# GPSBoard_L30.net
KiCad netlist of a schematic drawn in Altium Designer
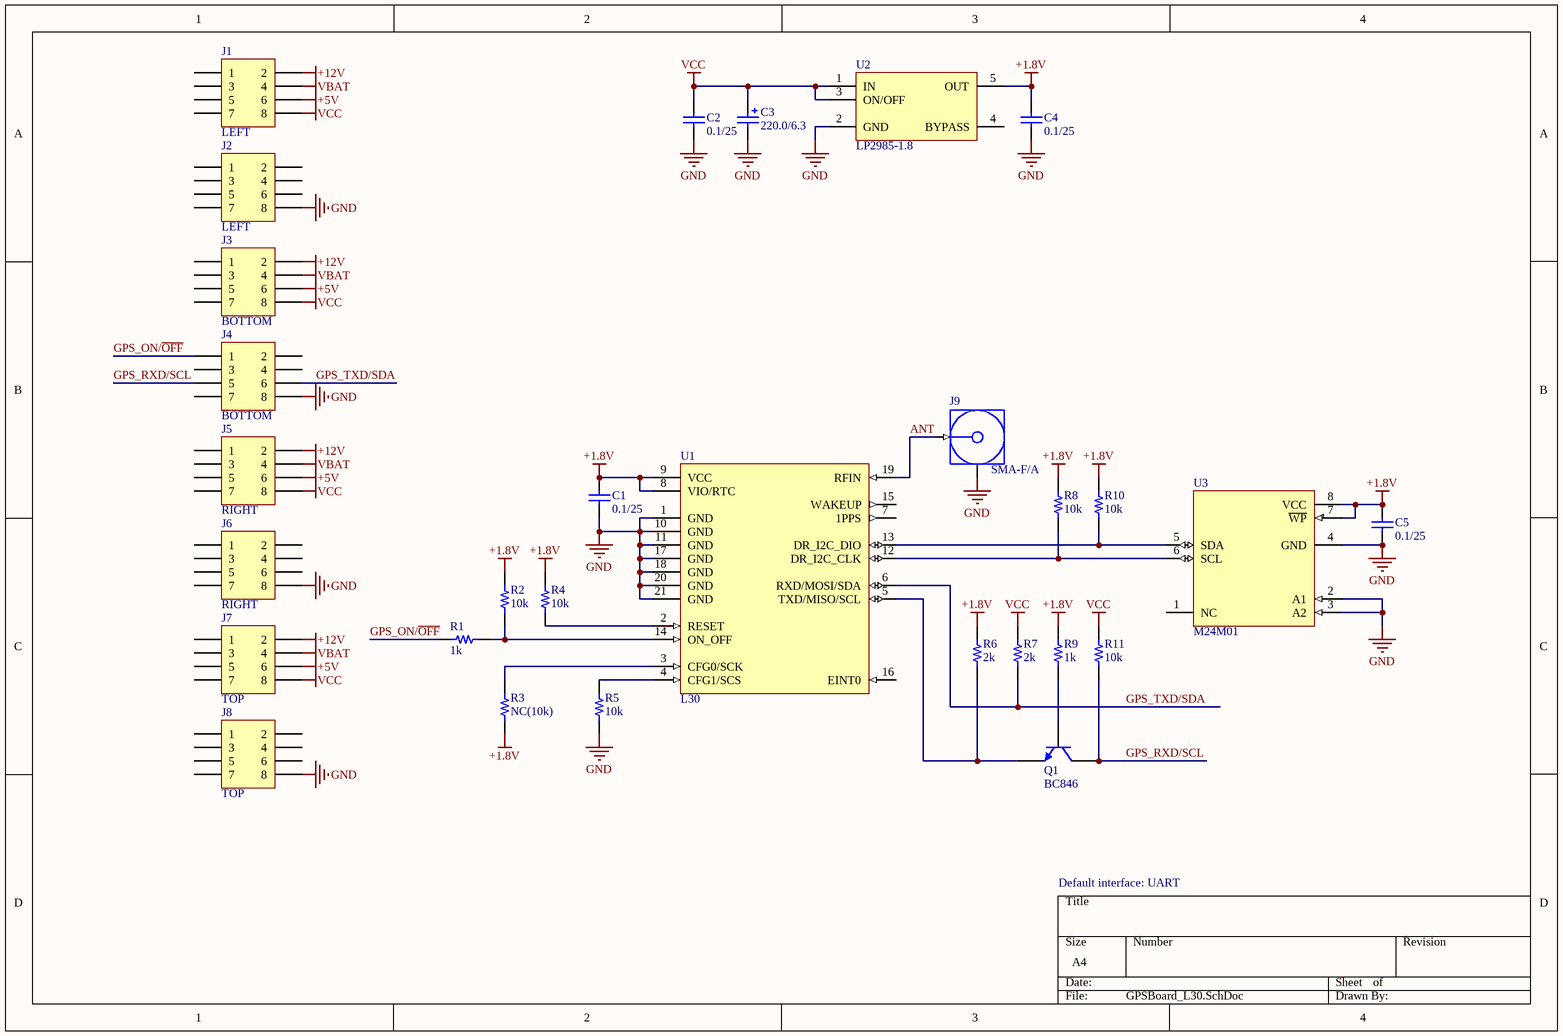
[diagram p0: GPSBoard_L30.SchDoc]

(export (version "E")
  (design (tool "Eeschema 10.0.6"))
  (components
    (comp (ref "C1")
      (value "0.1/25")
      (footprint "CAP0402")
      (description "Ceramic chip capacitor 0402")
      (fields
        (field (name "PARTNUMBER") "CAP0402")
        (field (name "VOLTAGE") "25")
        (field (name "AUTHOR") "oiezhov")
      )
      (libsource (lib "Library") (part "Capacitor"))
    )
    (comp (ref "C2")
      (value "0.1/25")
      (footprint "CAP0402")
      (description "Ceramic chip capacitor 0402")
      (fields
        (field (name "PARTNUMBER") "CAP0402")
        (field (name "VOLTAGE") "25")
        (field (name "AUTHOR") "oiezhov")
      )
      (libsource (lib "Library") (part "Capacitor"))
    )
    (comp (ref "C3")
      (value "220.0/6.3")
      (footprint "SMC")
      (description "Standard tantalum SMT capacitor, size C")
      (fields
        (field (name "PARTNUMBER") "TAJC")
        (field (name "VOLTAGE") "6.3")
        (field (name "AUTHOR") "oiezhov")
      )
      (libsource (lib "Library") (part "Polar capacitor"))
    )
    (comp (ref "C4")
      (value "0.1/25")
      (footprint "CAP0402")
      (description "Ceramic chip capacitor 0402")
      (fields
        (field (name "PARTNUMBER") "CAP0402")
        (field (name "VOLTAGE") "25")
        (field (name "AUTHOR") "oiezhov")
      )
      (libsource (lib "Library") (part "Capacitor"))
    )
    (comp (ref "C5")
      (value "0.1/25")
      (footprint "CAP0402")
      (description "Ceramic chip capacitor 0402")
      (fields
        (field (name "PARTNUMBER") "CAP0402")
        (field (name "VOLTAGE") "25")
        (field (name "AUTHOR") "oiezhov")
      )
      (libsource (lib "Library") (part "Capacitor"))
    )
    (comp (ref "J1")
      (value "LEFT")
      (footprint "PBDM-8")
      (description "2x4-pin header, pitch 2.54 mm")
      (fields (field (name "PARTNUMBER") "PBDM-8") (field (name "AUTHOR") "oiezhov"))
      (libsource (lib "Library") (part "8-pin dual row connector"))
    )
    (comp (ref "J2")
      (value "LEFT")
      (footprint "PBDM-8")
      (description "2x4-pin header, pitch 2.54 mm")
      (fields (field (name "PARTNUMBER") "PBDM-8") (field (name "AUTHOR") "oiezhov"))
      (libsource (lib "Library") (part "8-pin dual row connector"))
    )
    (comp (ref "J3")
      (value "BOTTOM")
      (footprint "PBDM-8")
      (description "2x4-pin header, pitch 2.54 mm")
      (fields (field (name "PARTNUMBER") "PBDM-8") (field (name "AUTHOR") "oiezhov"))
      (libsource (lib "Library") (part "8-pin dual row connector"))
    )
    (comp (ref "J4")
      (value "BOTTOM")
      (footprint "PBDM-8")
      (description "2x4-pin header, pitch 2.54 mm")
      (fields (field (name "PARTNUMBER") "PBDM-8") (field (name "AUTHOR") "oiezhov"))
      (libsource (lib "Library") (part "8-pin dual row connector"))
    )
    (comp (ref "J5")
      (value "RIGHT")
      (footprint "PBDM-8")
      (description "2x4-pin header, pitch 2.54 mm")
      (fields (field (name "PARTNUMBER") "PBDM-8") (field (name "AUTHOR") "oiezhov"))
      (libsource (lib "Library") (part "8-pin dual row connector"))
    )
    (comp (ref "J6")
      (value "RIGHT")
      (footprint "PBDM-8")
      (description "2x4-pin header, pitch 2.54 mm")
      (fields (field (name "PARTNUMBER") "PBDM-8") (field (name "AUTHOR") "oiezhov"))
      (libsource (lib "Library") (part "8-pin dual row connector"))
    )
    (comp (ref "J7")
      (value "TOP")
      (footprint "PBDM-8")
      (description "2x4-pin header, pitch 2.54 mm")
      (fields (field (name "PARTNUMBER") "PBDM-8") (field (name "AUTHOR") "oiezhov"))
      (libsource (lib "Library") (part "8-pin dual row connector"))
    )
    (comp (ref "J8")
      (value "TOP")
      (footprint "PBDM-8")
      (description "2x4-pin header, pitch 2.54 mm")
      (fields (field (name "PARTNUMBER") "PBDM-8") (field (name "AUTHOR") "oiezhov"))
      (libsource (lib "Library") (part "8-pin dual row connector"))
    )
    (comp (ref "J9")
      (value "SMA-F/A")
      (footprint "SMA-F/A")
      (description "Angle SMA female connector")
      (fields (field (name "AUTHOR") "oiezhov"))
      (libsource (lib "Library") (part "SMA"))
    )
    (comp (ref "Q1")
      (value "BC846")
      (footprint "SOT23")
      (description "NPN Silicon AF Transistor")
      (fields (field (name "AUTHOR") "oiezhov"))
      (libsource (lib "Library") (part "BC846"))
    )
    (comp (ref "R1")
      (value "1k")
      (footprint "RES0402")
      (description "Ceramic chip resistor")
      (fields (field (name "PARTNUMBER") "RES0402") (field (name "AUTHOR") "oiezhov"))
      (libsource (lib "Library") (part "Resistor"))
    )
    (comp (ref "R2")
      (value "10k")
      (footprint "RES0402")
      (description "Ceramic chip resistor")
      (fields (field (name "PARTNUMBER") "RES0402") (field (name "AUTHOR") "oiezhov"))
      (libsource (lib "Library") (part "Resistor"))
    )
    (comp (ref "R3")
      (value "NC(10k)")
      (footprint "RES0402")
      (description "Ceramic chip resistor")
      (fields (field (name "PARTNUMBER") "RES0402") (field (name "AUTHOR") "oiezhov"))
      (libsource (lib "Library") (part "Resistor"))
    )
    (comp (ref "R4")
      (value "10k")
      (footprint "RES0402")
      (description "Ceramic chip resistor")
      (fields (field (name "PARTNUMBER") "RES0402") (field (name "AUTHOR") "oiezhov"))
      (libsource (lib "Library") (part "Resistor"))
    )
    (comp (ref "R5")
      (value "10k")
      (footprint "RES0402")
      (description "Ceramic chip resistor")
      (fields (field (name "PARTNUMBER") "RES0402") (field (name "AUTHOR") "oiezhov"))
      (libsource (lib "Library") (part "Resistor"))
    )
    (comp (ref "R6")
      (value "2k")
      (footprint "RES0402")
      (description "Ceramic chip resistor")
      (fields (field (name "PARTNUMBER") "RES0402") (field (name "AUTHOR") "oiezhov"))
      (libsource (lib "Library") (part "Resistor"))
    )
    (comp (ref "R7")
      (value "2k")
      (footprint "RES0402")
      (description "Ceramic chip resistor")
      (fields (field (name "PARTNUMBER") "RES0402") (field (name "AUTHOR") "oiezhov"))
      (libsource (lib "Library") (part "Resistor"))
    )
    (comp (ref "R8")
      (value "10k")
      (footprint "RES0402")
      (description "Ceramic chip resistor")
      (fields (field (name "PARTNUMBER") "RES0402") (field (name "AUTHOR") "oiezhov"))
      (libsource (lib "Library") (part "Resistor"))
    )
    (comp (ref "R9")
      (value "1k")
      (footprint "RES0402")
      (description "Ceramic chip resistor")
      (fields (field (name "PARTNUMBER") "RES0402") (field (name "AUTHOR") "oiezhov"))
      (libsource (lib "Library") (part "Resistor"))
    )
    (comp (ref "R10")
      (value "10k")
      (footprint "RES0402")
      (description "Ceramic chip resistor")
      (fields (field (name "PARTNUMBER") "RES0402") (field (name "AUTHOR") "oiezhov"))
      (libsource (lib "Library") (part "Resistor"))
    )
    (comp (ref "R11")
      (value "10k")
      (footprint "RES0402")
      (description "Ceramic chip resistor")
      (fields (field (name "PARTNUMBER") "RES0402") (field (name "AUTHOR") "oiezhov"))
      (libsource (lib "Library") (part "Resistor"))
    )
    (comp (ref "U1")
      (value "L30")
      (footprint "Quectel_L30")
      (description "GPS Engine")
      (fields (field (name "AUTHOR") "oiezhov"))
      (libsource (lib "Library") (part "L30"))
    )
    (comp (ref "U2")
      (value "LP2985-1.8")
      (footprint "SOT23-5")
      (description "150-mA Low-Noise Low-Dropout Regulator with Shutdown")
      (fields (field (name "AUTHOR") "oiezhov"))
      (libsource (lib "Library") (part "5-pin voltage regulator with ON/OFF and BYPASS"))
    )
    (comp (ref "U3")
      (value "M24M01")
      (footprint "SO8")
      (description "1-Mbit serial I²C bus EEPROM")
      (fields (field (name "AUTHOR") "oiezhov"))
      (libsource (lib "Library") (part "8-pin I2C EEPROM with NC"))
    )
  )
  (nets
    (net (code "1") (name "+1.8V") (class "Default")
      (node (ref "C1") (pin "2") (pinfunction "2_2") (pintype "passive"))
      (node (ref "C4") (pin "2") (pinfunction "2_2") (pintype "passive"))
      (node (ref "C5") (pin "2") (pinfunction "2_2") (pintype "passive"))
      (node (ref "R10") (pin "2") (pinfunction "2_2") (pintype "passive"))
      (node (ref "R2") (pin "1") (pinfunction "1_1") (pintype "passive"))
      (node (ref "R3") (pin "1") (pinfunction "1_1") (pintype "passive"))
      (node (ref "R4") (pin "1") (pinfunction "1_1") (pintype "passive"))
      (node (ref "R6") (pin "1") (pinfunction "1_1") (pintype "passive"))
      (node (ref "R8") (pin "2") (pinfunction "2_2") (pintype "passive"))
      (node (ref "R9") (pin "1") (pinfunction "1_1") (pintype "passive"))
      (node (ref "U1") (pin "8") (pinfunction "VIO/RTC_8") (pintype "power_in"))
      (node (ref "U1") (pin "9") (pinfunction "VCC_9") (pintype "power_in"))
      (node (ref "U2") (pin "5") (pinfunction "OUT_5") (pintype "passive"))
      (node (ref "U3") (pin "7") (pinfunction "~{WP}_7") (pintype "input"))
      (node (ref "U3") (pin "8") (pinfunction "VCC_8") (pintype "power_in"))
    )
    (net (code "2") (name "+5V") (class "Default")
      (node (ref "J1") (pin "6") (pinfunction "6_6") (pintype "passive"))
      (node (ref "J3") (pin "6") (pinfunction "6_6") (pintype "passive"))
      (node (ref "J5") (pin "6") (pinfunction "6_6") (pintype "passive"))
      (node (ref "J7") (pin "6") (pinfunction "6_6") (pintype "passive"))
    )
    (net (code "3") (name "+12V") (class "Default")
      (node (ref "J1") (pin "2") (pinfunction "2_2") (pintype "passive"))
      (node (ref "J3") (pin "2") (pinfunction "2_2") (pintype "passive"))
      (node (ref "J5") (pin "2") (pinfunction "2_2") (pintype "passive"))
      (node (ref "J7") (pin "2") (pinfunction "2_2") (pintype "passive"))
    )
    (net (code "4") (name "/ANT") (class "Default")
      (node (ref "J9") (pin "1") (pinfunction "Signal_1") (pintype "input"))
      (node (ref "U1") (pin "19") (pinfunction "RFIN_19") (pintype "input"))
    )
    (net (code "5") (name "/GPS_ON{slash}~{OFF}") (class "Default")
      (node (ref "J4") (pin "1") (pinfunction "1_1") (pintype "passive"))
      (node (ref "R1") (pin "1") (pinfunction "1_1") (pintype "passive"))
    )
    (net (code "6") (name "/GPS_RXD{slash}SCL") (class "Default")
      (node (ref "J4") (pin "5") (pinfunction "5_5") (pintype "passive"))
      (node (ref "Q1") (pin "3") (pinfunction "C_3") (pintype "passive"))
      (node (ref "R11") (pin "2") (pinfunction "2_2") (pintype "passive"))
    )
    (net (code "7") (name "/GPS_TXD{slash}SDA") (class "Default")
      (node (ref "J4") (pin "6") (pinfunction "6_6") (pintype "passive"))
      (node (ref "R7") (pin "2") (pinfunction "2_2") (pintype "passive"))
      (node (ref "U1") (pin "6") (pinfunction "RXD/MOSI/SDA_6") (pintype "bidirectional"))
    )
    (net (code "8") (name "GND") (class "Default")
      (node (ref "C1") (pin "1") (pinfunction "1_1") (pintype "passive"))
      (node (ref "C2") (pin "1") (pinfunction "1_1") (pintype "passive"))
      (node (ref "C3") (pin "1") (pinfunction "1_1") (pintype "passive"))
      (node (ref "C4") (pin "1") (pinfunction "1_1") (pintype "passive"))
      (node (ref "C5") (pin "1") (pinfunction "1_1") (pintype "passive"))
      (node (ref "J2") (pin "8") (pinfunction "8_8") (pintype "passive"))
      (node (ref "J4") (pin "8") (pinfunction "8_8") (pintype "passive"))
      (node (ref "J6") (pin "8") (pinfunction "8_8") (pintype "passive"))
      (node (ref "J8") (pin "8") (pinfunction "8_8") (pintype "passive"))
      (node (ref "J9") (pin "2") (pinfunction "GND_2") (pintype "power_in"))
      (node (ref "R5") (pin "1") (pinfunction "1_1") (pintype "passive"))
      (node (ref "U1") (pin "1") (pinfunction "GND_1") (pintype "power_in"))
      (node (ref "U1") (pin "10") (pinfunction "GND_10") (pintype "power_in"))
      (node (ref "U1") (pin "11") (pinfunction "GND_11") (pintype "power_in"))
      (node (ref "U1") (pin "17") (pinfunction "GND_17") (pintype "power_in"))
      (node (ref "U1") (pin "18") (pinfunction "GND_18") (pintype "power_in"))
      (node (ref "U1") (pin "20") (pinfunction "GND_20") (pintype "power_in"))
      (node (ref "U1") (pin "21") (pinfunction "GND_21") (pintype "power_in"))
      (node (ref "U2") (pin "2") (pinfunction "GND_2") (pintype "passive"))
      (node (ref "U3") (pin "2") (pinfunction "A1_2") (pintype "input"))
      (node (ref "U3") (pin "3") (pinfunction "A2_3") (pintype "input"))
      (node (ref "U3") (pin "4") (pinfunction "GND_4") (pintype "power_in"))
    )
    (net (code "9") (name "Net-(Q1-B)") (class "Default")
      (node (ref "Q1") (pin "2") (pinfunction "B_2") (pintype "passive"))
      (node (ref "R9") (pin "2") (pinfunction "2_2") (pintype "passive"))
    )
    (net (code "10") (name "Net-(Q1-E)") (class "Default")
      (node (ref "Q1") (pin "1") (pinfunction "E_1") (pintype "passive"))
      (node (ref "R6") (pin "2") (pinfunction "2_2") (pintype "passive"))
      (node (ref "U1") (pin "5") (pinfunction "TXD/MISO/SCL_5") (pintype "bidirectional"))
    )
    (net (code "11") (name "Net-(U1-CFG0{slash}SCK)") (class "Default")
      (node (ref "R3") (pin "2") (pinfunction "2_2") (pintype "passive"))
      (node (ref "U1") (pin "3") (pinfunction "CFG0/SCK_3") (pintype "input"))
    )
    (net (code "12") (name "Net-(U1-CFG1{slash}SCS)") (class "Default")
      (node (ref "R5") (pin "2") (pinfunction "2_2") (pintype "passive"))
      (node (ref "U1") (pin "4") (pinfunction "CFG1/SCS_4") (pintype "input"))
    )
    (net (code "13") (name "Net-(U1-DR_I2C_CLK)") (class "Default")
      (node (ref "R8") (pin "1") (pinfunction "1_1") (pintype "passive"))
      (node (ref "U1") (pin "12") (pinfunction "DR_I2C_CLK_12") (pintype "bidirectional"))
      (node (ref "U3") (pin "6") (pinfunction "SCL_6") (pintype "bidirectional"))
    )
    (net (code "14") (name "Net-(U1-DR_I2C_DIO)") (class "Default")
      (node (ref "R10") (pin "1") (pinfunction "1_1") (pintype "passive"))
      (node (ref "U1") (pin "13") (pinfunction "DR_I2C_DIO_13") (pintype "bidirectional"))
      (node (ref "U3") (pin "5") (pinfunction "SDA_5") (pintype "bidirectional"))
    )
    (net (code "15") (name "Net-(U1-ON_OFF)") (class "Default")
      (node (ref "R1") (pin "2") (pinfunction "2_2") (pintype "passive"))
      (node (ref "R2") (pin "2") (pinfunction "2_2") (pintype "passive"))
      (node (ref "U1") (pin "14") (pinfunction "ON_OFF_14") (pintype "input"))
    )
    (net (code "16") (name "Net-(U1-RESET)") (class "Default")
      (node (ref "R4") (pin "2") (pinfunction "2_2") (pintype "passive"))
      (node (ref "U1") (pin "2") (pinfunction "RESET_2") (pintype "input"))
    )
    (net (code "17") (name "VBAT") (class "Default")
      (node (ref "J1") (pin "4") (pinfunction "4_4") (pintype "passive"))
      (node (ref "J3") (pin "4") (pinfunction "4_4") (pintype "passive"))
      (node (ref "J5") (pin "4") (pinfunction "4_4") (pintype "passive"))
      (node (ref "J7") (pin "4") (pinfunction "4_4") (pintype "passive"))
    )
    (net (code "18") (name "VCC") (class "Default")
      (node (ref "C2") (pin "2") (pinfunction "2_2") (pintype "passive"))
      (node (ref "C3") (pin "2") (pinfunction "2_2") (pintype "passive"))
      (node (ref "J1") (pin "8") (pinfunction "8_8") (pintype "passive"))
      (node (ref "J3") (pin "8") (pinfunction "8_8") (pintype "passive"))
      (node (ref "J5") (pin "8") (pinfunction "8_8") (pintype "passive"))
      (node (ref "J7") (pin "8") (pinfunction "8_8") (pintype "passive"))
      (node (ref "R11") (pin "1") (pinfunction "1_1") (pintype "passive"))
      (node (ref "R7") (pin "1") (pinfunction "1_1") (pintype "passive"))
      (node (ref "U2") (pin "1") (pinfunction "IN_1") (pintype "passive"))
      (node (ref "U2") (pin "3") (pinfunction "ON/OFF_3") (pintype "passive"))
    )
    (net (code "19") (name "unconnected-(J1-Pad1)") (class "Default")
      (node (ref "J1") (pin "1") (pinfunction "1_1") (pintype "passive"))
    )
    (net (code "20") (name "unconnected-(J1-Pad3)") (class "Default")
      (node (ref "J1") (pin "3") (pinfunction "3_3") (pintype "passive"))
    )
    (net (code "21") (name "unconnected-(J1-Pad5)") (class "Default")
      (node (ref "J1") (pin "5") (pinfunction "5_5") (pintype "passive"))
    )
    (net (code "22") (name "unconnected-(J1-Pad7)") (class "Default")
      (node (ref "J1") (pin "7") (pinfunction "7_7") (pintype "passive"))
    )
    (net (code "23") (name "unconnected-(J2-Pad1)") (class "Default")
      (node (ref "J2") (pin "1") (pinfunction "1_1") (pintype "passive"))
    )
    (net (code "24") (name "unconnected-(J2-Pad2)") (class "Default")
      (node (ref "J2") (pin "2") (pinfunction "2_2") (pintype "passive"))
    )
    (net (code "25") (name "unconnected-(J2-Pad3)") (class "Default")
      (node (ref "J2") (pin "3") (pinfunction "3_3") (pintype "passive"))
    )
    (net (code "26") (name "unconnected-(J2-Pad4)") (class "Default")
      (node (ref "J2") (pin "4") (pinfunction "4_4") (pintype "passive"))
    )
    (net (code "27") (name "unconnected-(J2-Pad5)") (class "Default")
      (node (ref "J2") (pin "5") (pinfunction "5_5") (pintype "passive"))
    )
    (net (code "28") (name "unconnected-(J2-Pad6)") (class "Default")
      (node (ref "J2") (pin "6") (pinfunction "6_6") (pintype "passive"))
    )
    (net (code "29") (name "unconnected-(J2-Pad7)") (class "Default")
      (node (ref "J2") (pin "7") (pinfunction "7_7") (pintype "passive"))
    )
    (net (code "30") (name "unconnected-(J3-Pad1)") (class "Default")
      (node (ref "J3") (pin "1") (pinfunction "1_1") (pintype "passive"))
    )
    (net (code "31") (name "unconnected-(J3-Pad3)") (class "Default")
      (node (ref "J3") (pin "3") (pinfunction "3_3") (pintype "passive"))
    )
    (net (code "32") (name "unconnected-(J3-Pad5)") (class "Default")
      (node (ref "J3") (pin "5") (pinfunction "5_5") (pintype "passive"))
    )
    (net (code "33") (name "unconnected-(J3-Pad7)") (class "Default")
      (node (ref "J3") (pin "7") (pinfunction "7_7") (pintype "passive"))
    )
    (net (code "34") (name "unconnected-(J4-Pad2)") (class "Default")
      (node (ref "J4") (pin "2") (pinfunction "2_2") (pintype "passive"))
    )
    (net (code "35") (name "unconnected-(J4-Pad3)") (class "Default")
      (node (ref "J4") (pin "3") (pinfunction "3_3") (pintype "passive"))
    )
    (net (code "36") (name "unconnected-(J4-Pad4)") (class "Default")
      (node (ref "J4") (pin "4") (pinfunction "4_4") (pintype "passive"))
    )
    (net (code "37") (name "unconnected-(J4-Pad7)") (class "Default")
      (node (ref "J4") (pin "7") (pinfunction "7_7") (pintype "passive"))
    )
    (net (code "38") (name "unconnected-(J5-Pad1)") (class "Default")
      (node (ref "J5") (pin "1") (pinfunction "1_1") (pintype "passive"))
    )
    (net (code "39") (name "unconnected-(J5-Pad3)") (class "Default")
      (node (ref "J5") (pin "3") (pinfunction "3_3") (pintype "passive"))
    )
    (net (code "40") (name "unconnected-(J5-Pad5)") (class "Default")
      (node (ref "J5") (pin "5") (pinfunction "5_5") (pintype "passive"))
    )
    (net (code "41") (name "unconnected-(J5-Pad7)") (class "Default")
      (node (ref "J5") (pin "7") (pinfunction "7_7") (pintype "passive"))
    )
    (net (code "42") (name "unconnected-(J6-Pad1)") (class "Default")
      (node (ref "J6") (pin "1") (pinfunction "1_1") (pintype "passive"))
    )
    (net (code "43") (name "unconnected-(J6-Pad2)") (class "Default")
      (node (ref "J6") (pin "2") (pinfunction "2_2") (pintype "passive"))
    )
    (net (code "44") (name "unconnected-(J6-Pad3)") (class "Default")
      (node (ref "J6") (pin "3") (pinfunction "3_3") (pintype "passive"))
    )
    (net (code "45") (name "unconnected-(J6-Pad4)") (class "Default")
      (node (ref "J6") (pin "4") (pinfunction "4_4") (pintype "passive"))
    )
    (net (code "46") (name "unconnected-(J6-Pad5)") (class "Default")
      (node (ref "J6") (pin "5") (pinfunction "5_5") (pintype "passive"))
    )
    (net (code "47") (name "unconnected-(J6-Pad6)") (class "Default")
      (node (ref "J6") (pin "6") (pinfunction "6_6") (pintype "passive"))
    )
    (net (code "48") (name "unconnected-(J6-Pad7)") (class "Default")
      (node (ref "J6") (pin "7") (pinfunction "7_7") (pintype "passive"))
    )
    (net (code "49") (name "unconnected-(J7-Pad1)") (class "Default")
      (node (ref "J7") (pin "1") (pinfunction "1_1") (pintype "passive"))
    )
    (net (code "50") (name "unconnected-(J7-Pad3)") (class "Default")
      (node (ref "J7") (pin "3") (pinfunction "3_3") (pintype "passive"))
    )
    (net (code "51") (name "unconnected-(J7-Pad5)") (class "Default")
      (node (ref "J7") (pin "5") (pinfunction "5_5") (pintype "passive"))
    )
    (net (code "52") (name "unconnected-(J7-Pad7)") (class "Default")
      (node (ref "J7") (pin "7") (pinfunction "7_7") (pintype "passive"))
    )
    (net (code "53") (name "unconnected-(J8-Pad1)") (class "Default")
      (node (ref "J8") (pin "1") (pinfunction "1_1") (pintype "passive"))
    )
    (net (code "54") (name "unconnected-(J8-Pad2)") (class "Default")
      (node (ref "J8") (pin "2") (pinfunction "2_2") (pintype "passive"))
    )
    (net (code "55") (name "unconnected-(J8-Pad3)") (class "Default")
      (node (ref "J8") (pin "3") (pinfunction "3_3") (pintype "passive"))
    )
    (net (code "56") (name "unconnected-(J8-Pad4)") (class "Default")
      (node (ref "J8") (pin "4") (pinfunction "4_4") (pintype "passive"))
    )
    (net (code "57") (name "unconnected-(J8-Pad5)") (class "Default")
      (node (ref "J8") (pin "5") (pinfunction "5_5") (pintype "passive"))
    )
    (net (code "58") (name "unconnected-(J8-Pad6)") (class "Default")
      (node (ref "J8") (pin "6") (pinfunction "6_6") (pintype "passive"))
    )
    (net (code "59") (name "unconnected-(J8-Pad7)") (class "Default")
      (node (ref "J8") (pin "7") (pinfunction "7_7") (pintype "passive"))
    )
    (net (code "60") (name "unconnected-(U1-1PPS-Pad7)") (class "Default")
      (node (ref "U1") (pin "7") (pinfunction "1PPS_7") (pintype "output"))
    )
    (net (code "61") (name "unconnected-(U1-EINT0-Pad16)") (class "Default")
      (node (ref "U1") (pin "16") (pinfunction "EINT0_16") (pintype "input"))
    )
    (net (code "62") (name "unconnected-(U1-WAKEUP-Pad15)") (class "Default")
      (node (ref "U1") (pin "15") (pinfunction "WAKEUP_15") (pintype "output"))
    )
    (net (code "63") (name "unconnected-(U2-BYPASS-Pad4)") (class "Default")
      (node (ref "U2") (pin "4") (pinfunction "BYPASS_4") (pintype "passive"))
    )
    (net (code "64") (name "unconnected-(U3-NC-Pad1)") (class "Default")
      (node (ref "U3") (pin "1") (pinfunction "NC_1") (pintype "passive"))
    )
  )
)
